# decoder.net
KiCad netlist of a schematic drawn in EAGLE
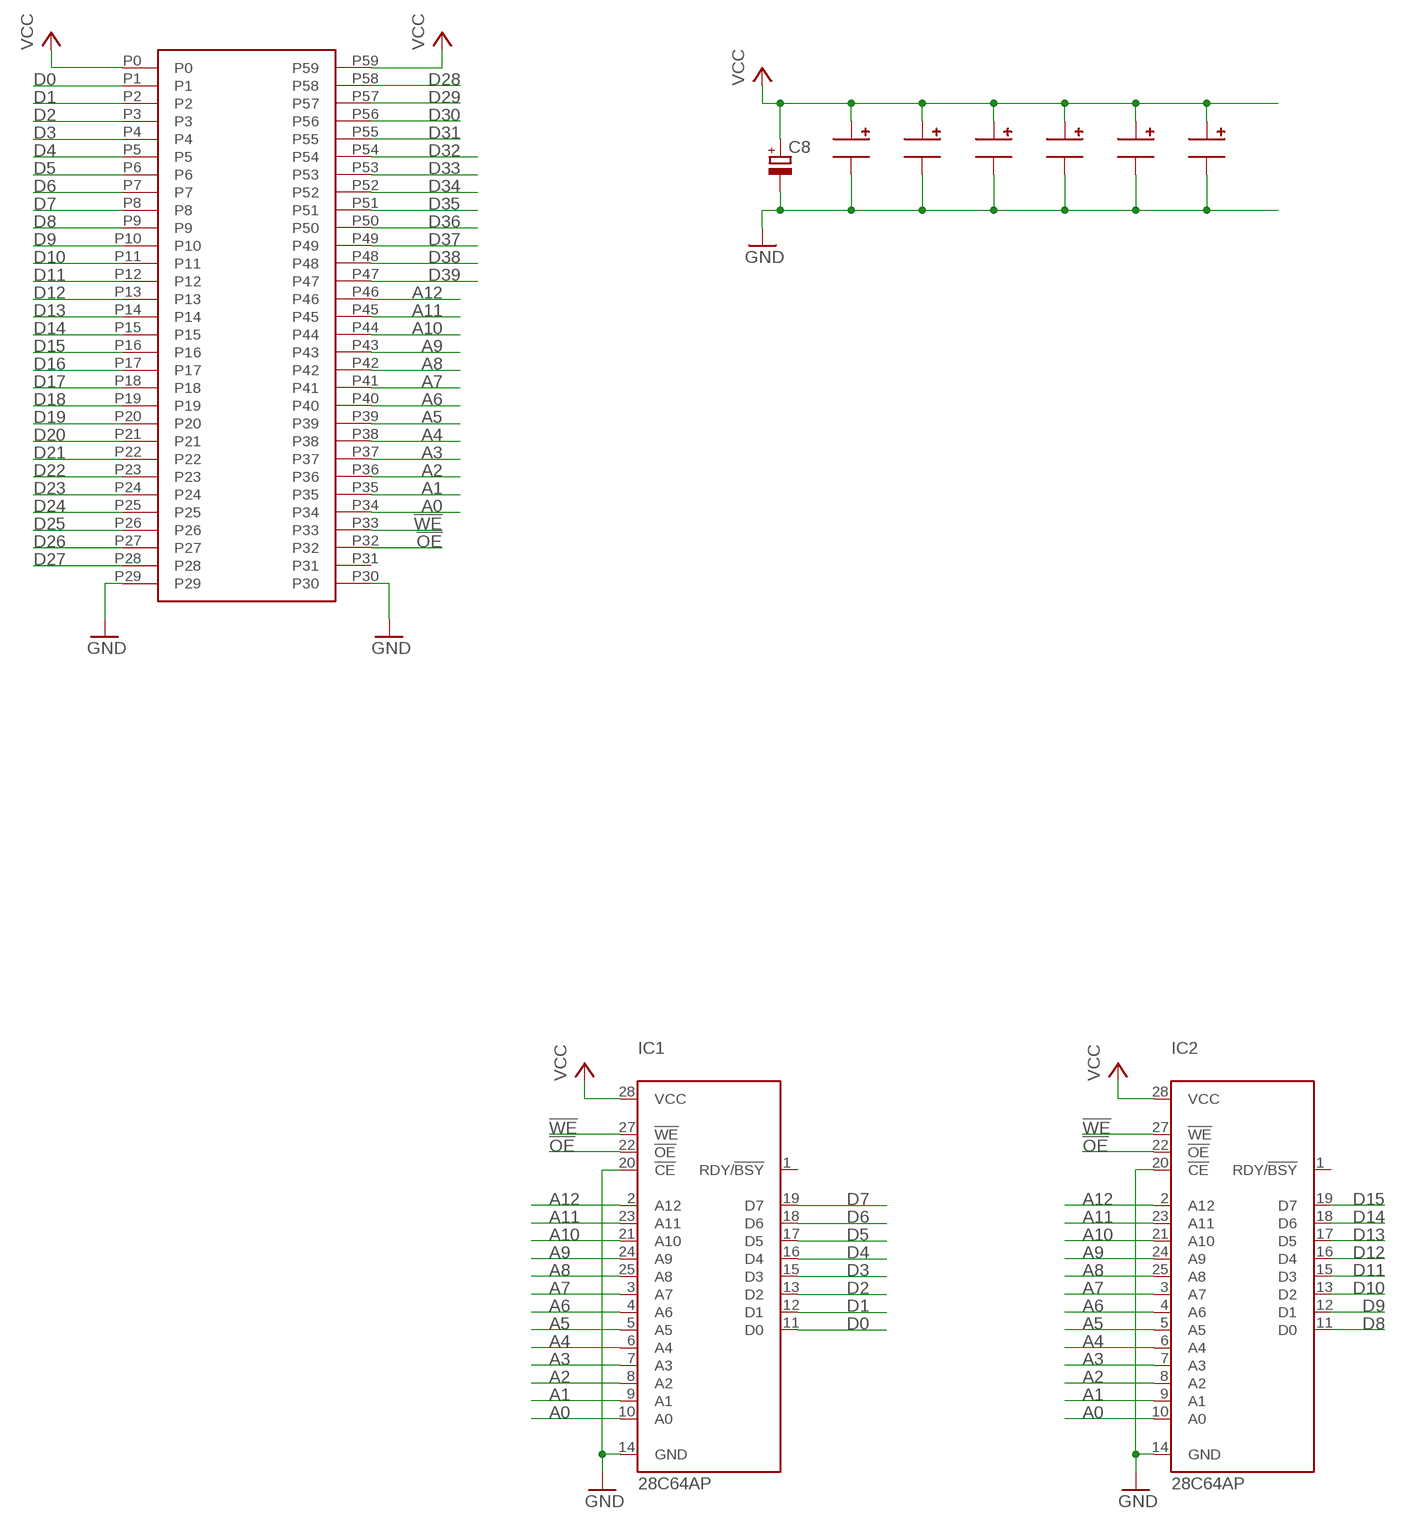
[diagram p0: schematic, sheet 1, part 1 of 2]
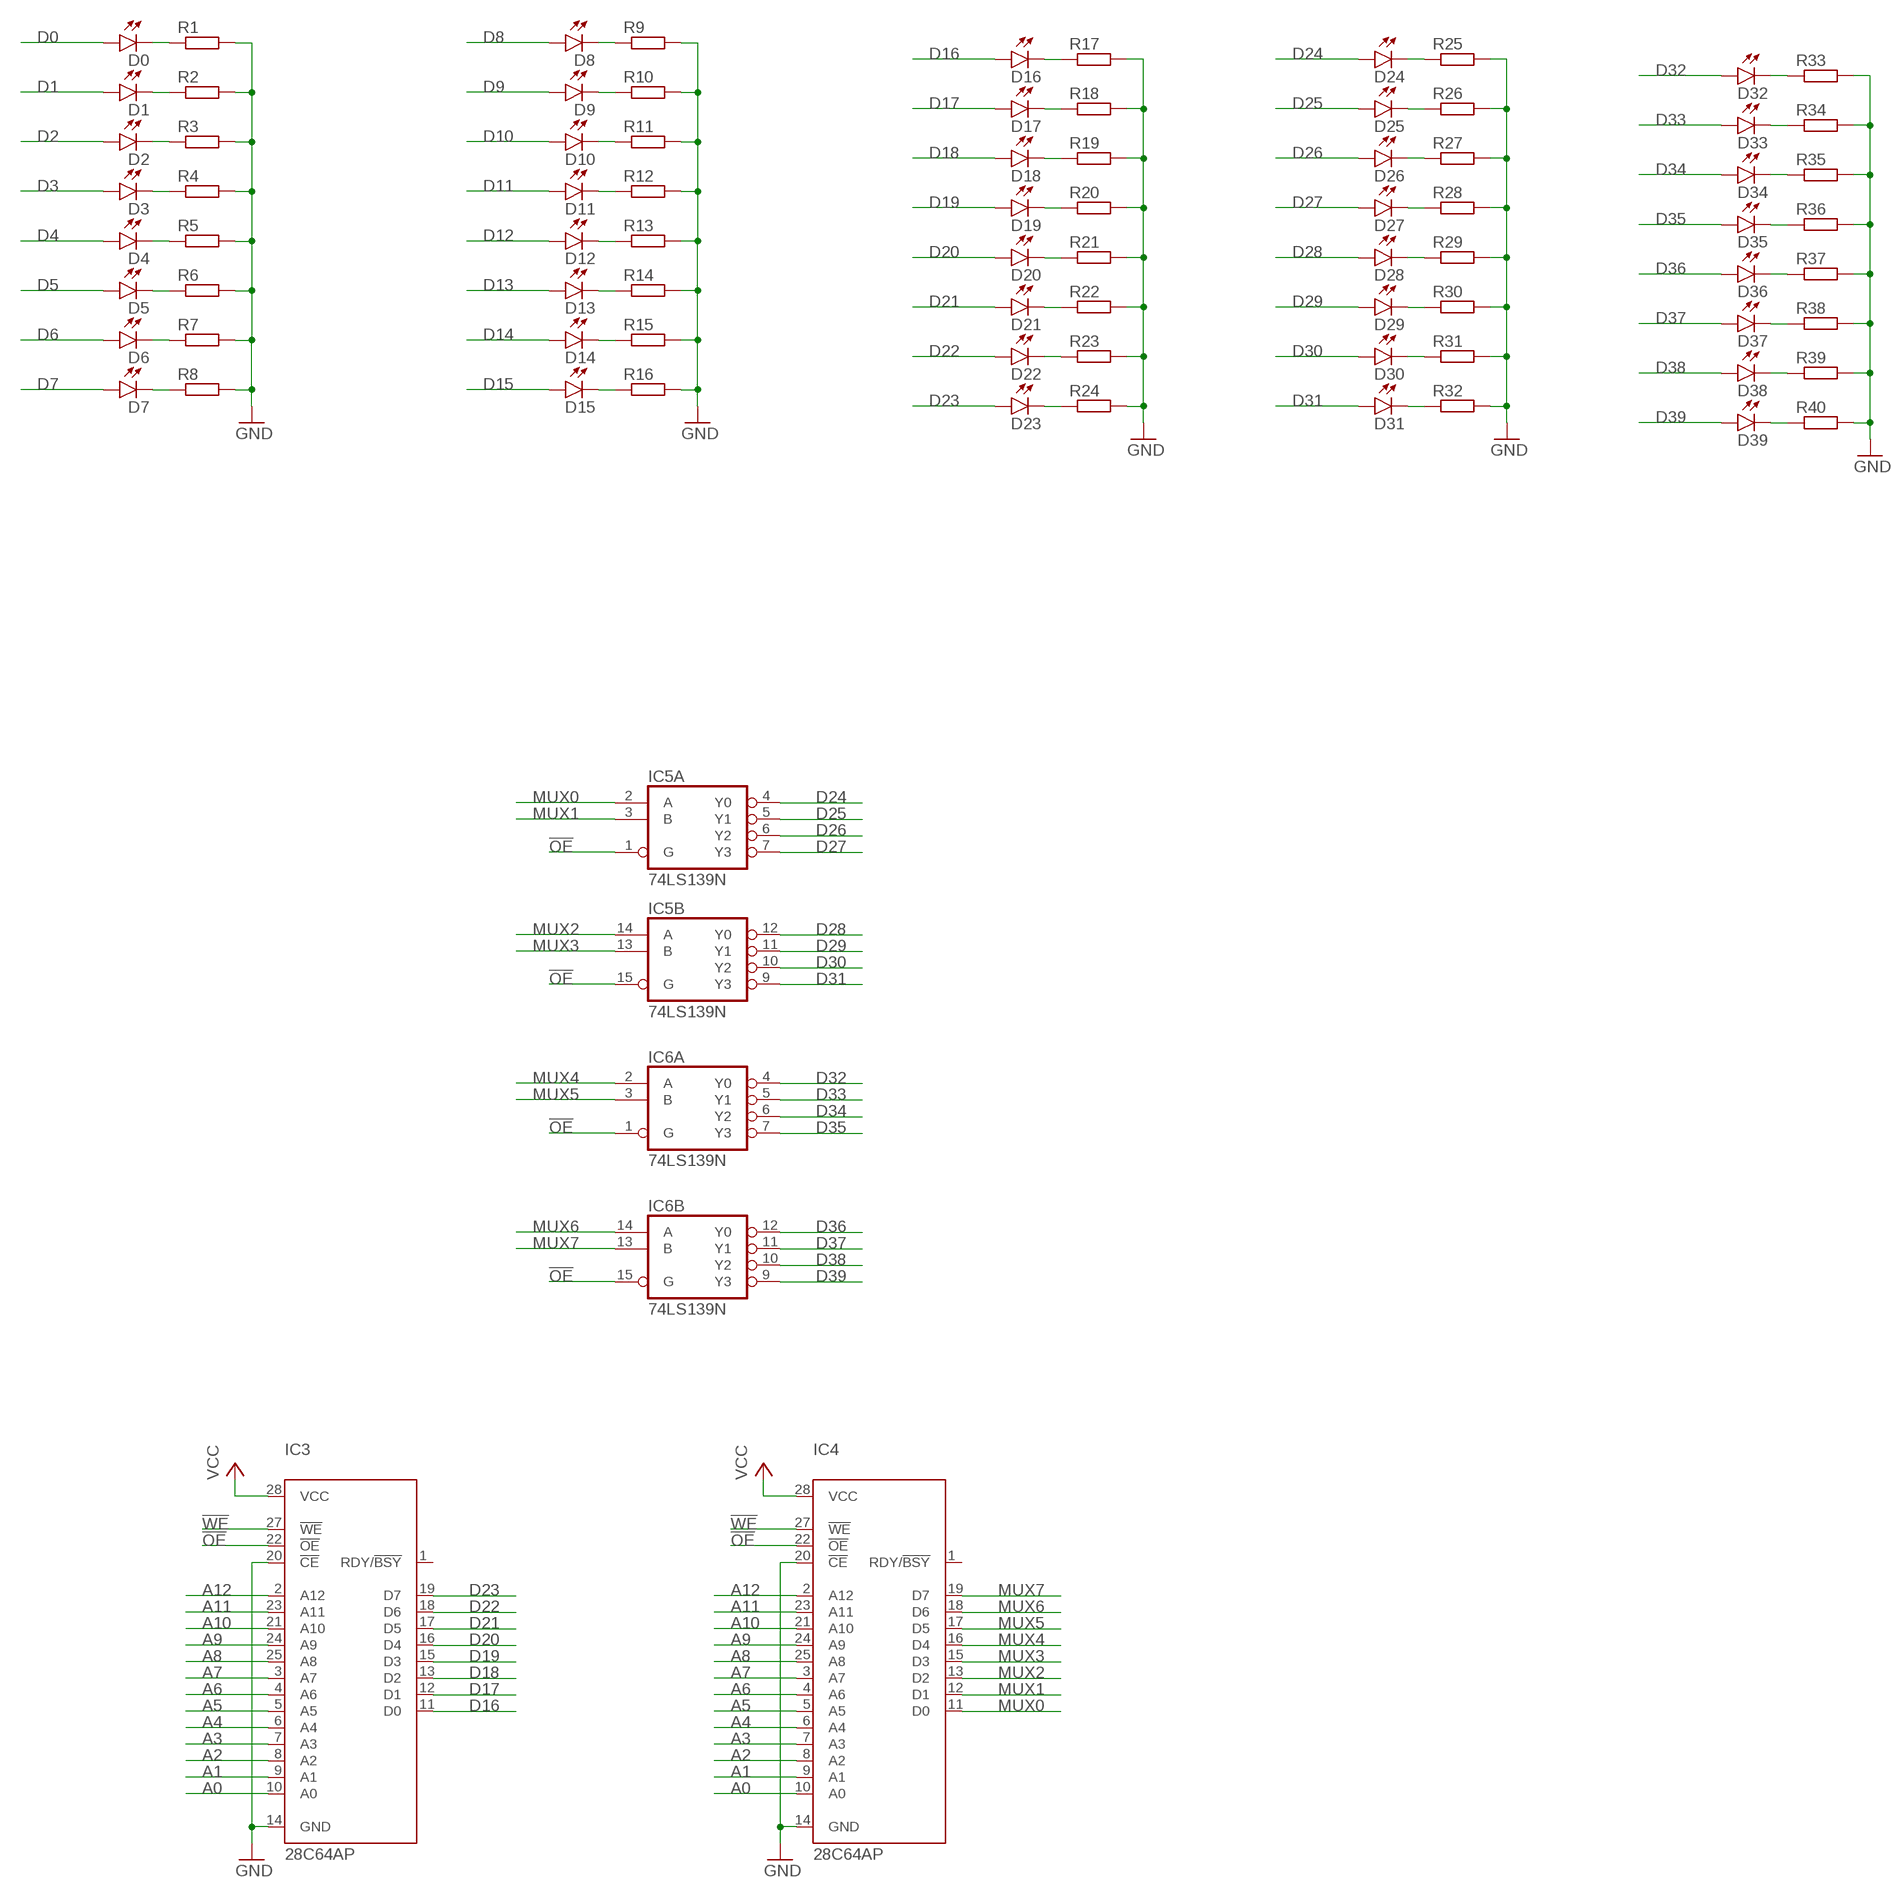
[diagram p1: schematic, sheet 1, part 2 of 2]

(export (version "E")
  (design (tool "Eeschema 10.0.6"))
  (components
    (comp (ref "C8")
      (value "CPOL-EUE2,5-6E")
      (footprint "eagle-import:E2,5-6E")
      (libsource (lib "eagle-import") (part "CPOL-EUE2,5-6E"))
    )
    (comp (ref "D0")
      (value "LEDSML1206")
      (footprint "eagle-import:SML1206")
      (libsource (lib "eagle-import") (part "LEDSML1206"))
    )
    (comp (ref "D1")
      (value "LEDSML1206")
      (footprint "eagle-import:SML1206")
      (libsource (lib "eagle-import") (part "LEDSML1206"))
    )
    (comp (ref "D2")
      (value "LEDSML1206")
      (footprint "eagle-import:SML1206")
      (libsource (lib "eagle-import") (part "LEDSML1206"))
    )
    (comp (ref "D3")
      (value "LEDSML1206")
      (footprint "eagle-import:SML1206")
      (libsource (lib "eagle-import") (part "LEDSML1206"))
    )
    (comp (ref "D4")
      (value "LEDSML1206")
      (footprint "eagle-import:SML1206")
      (libsource (lib "eagle-import") (part "LEDSML1206"))
    )
    (comp (ref "D5")
      (value "LEDSML1206")
      (footprint "eagle-import:SML1206")
      (libsource (lib "eagle-import") (part "LEDSML1206"))
    )
    (comp (ref "D6")
      (value "LEDSML1206")
      (footprint "eagle-import:SML1206")
      (libsource (lib "eagle-import") (part "LEDSML1206"))
    )
    (comp (ref "D7")
      (value "LEDSML1206")
      (footprint "eagle-import:SML1206")
      (libsource (lib "eagle-import") (part "LEDSML1206"))
    )
    (comp (ref "D8")
      (value "LEDSML1206")
      (footprint "eagle-import:SML1206")
      (libsource (lib "eagle-import") (part "LEDSML1206"))
    )
    (comp (ref "D9")
      (value "LEDSML1206")
      (footprint "eagle-import:SML1206")
      (libsource (lib "eagle-import") (part "LEDSML1206"))
    )
    (comp (ref "D10")
      (value "LEDSML1206")
      (footprint "eagle-import:SML1206")
      (libsource (lib "eagle-import") (part "LEDSML1206"))
    )
    (comp (ref "D11")
      (value "LEDSML1206")
      (footprint "eagle-import:SML1206")
      (libsource (lib "eagle-import") (part "LEDSML1206"))
    )
    (comp (ref "D12")
      (value "LEDSML1206")
      (footprint "eagle-import:SML1206")
      (libsource (lib "eagle-import") (part "LEDSML1206"))
    )
    (comp (ref "D13")
      (value "LEDSML1206")
      (footprint "eagle-import:SML1206")
      (libsource (lib "eagle-import") (part "LEDSML1206"))
    )
    (comp (ref "D14")
      (value "LEDSML1206")
      (footprint "eagle-import:SML1206")
      (libsource (lib "eagle-import") (part "LEDSML1206"))
    )
    (comp (ref "D15")
      (value "LEDSML1206")
      (footprint "eagle-import:SML1206")
      (libsource (lib "eagle-import") (part "LEDSML1206"))
    )
    (comp (ref "D16")
      (value "LEDSML1206")
      (footprint "eagle-import:SML1206")
      (libsource (lib "eagle-import") (part "LEDSML1206"))
    )
    (comp (ref "D17")
      (value "LEDSML1206")
      (footprint "eagle-import:SML1206")
      (libsource (lib "eagle-import") (part "LEDSML1206"))
    )
    (comp (ref "D18")
      (value "LEDSML1206")
      (footprint "eagle-import:SML1206")
      (libsource (lib "eagle-import") (part "LEDSML1206"))
    )
    (comp (ref "D19")
      (value "LEDSML1206")
      (footprint "eagle-import:SML1206")
      (libsource (lib "eagle-import") (part "LEDSML1206"))
    )
    (comp (ref "D20")
      (value "LEDSML1206")
      (footprint "eagle-import:SML1206")
      (libsource (lib "eagle-import") (part "LEDSML1206"))
    )
    (comp (ref "D21")
      (value "LEDSML1206")
      (footprint "eagle-import:SML1206")
      (libsource (lib "eagle-import") (part "LEDSML1206"))
    )
    (comp (ref "D22")
      (value "LEDSML1206")
      (footprint "eagle-import:SML1206")
      (libsource (lib "eagle-import") (part "LEDSML1206"))
    )
    (comp (ref "D23")
      (value "LEDSML1206")
      (footprint "eagle-import:SML1206")
      (libsource (lib "eagle-import") (part "LEDSML1206"))
    )
    (comp (ref "D24")
      (value "LEDSML1206")
      (footprint "eagle-import:SML1206")
      (libsource (lib "eagle-import") (part "LEDSML1206"))
    )
    (comp (ref "D25")
      (value "LEDSML1206")
      (footprint "eagle-import:SML1206")
      (libsource (lib "eagle-import") (part "LEDSML1206"))
    )
    (comp (ref "D26")
      (value "LEDSML1206")
      (footprint "eagle-import:SML1206")
      (libsource (lib "eagle-import") (part "LEDSML1206"))
    )
    (comp (ref "D27")
      (value "LEDSML1206")
      (footprint "eagle-import:SML1206")
      (libsource (lib "eagle-import") (part "LEDSML1206"))
    )
    (comp (ref "D28")
      (value "LEDSML1206")
      (footprint "eagle-import:SML1206")
      (libsource (lib "eagle-import") (part "LEDSML1206"))
    )
    (comp (ref "D29")
      (value "LEDSML1206")
      (footprint "eagle-import:SML1206")
      (libsource (lib "eagle-import") (part "LEDSML1206"))
    )
    (comp (ref "D30")
      (value "LEDSML1206")
      (footprint "eagle-import:SML1206")
      (libsource (lib "eagle-import") (part "LEDSML1206"))
    )
    (comp (ref "D31")
      (value "LEDSML1206")
      (footprint "eagle-import:SML1206")
      (libsource (lib "eagle-import") (part "LEDSML1206"))
    )
    (comp (ref "D32")
      (value "LEDSML1206")
      (footprint "eagle-import:SML1206")
      (libsource (lib "eagle-import") (part "LEDSML1206"))
    )
    (comp (ref "D33")
      (value "LEDSML1206")
      (footprint "eagle-import:SML1206")
      (libsource (lib "eagle-import") (part "LEDSML1206"))
    )
    (comp (ref "D34")
      (value "LEDSML1206")
      (footprint "eagle-import:SML1206")
      (libsource (lib "eagle-import") (part "LEDSML1206"))
    )
    (comp (ref "D35")
      (value "LEDSML1206")
      (footprint "eagle-import:SML1206")
      (libsource (lib "eagle-import") (part "LEDSML1206"))
    )
    (comp (ref "D36")
      (value "LEDSML1206")
      (footprint "eagle-import:SML1206")
      (libsource (lib "eagle-import") (part "LEDSML1206"))
    )
    (comp (ref "D37")
      (value "LEDSML1206")
      (footprint "eagle-import:SML1206")
      (libsource (lib "eagle-import") (part "LEDSML1206"))
    )
    (comp (ref "D38")
      (value "LEDSML1206")
      (footprint "eagle-import:SML1206")
      (libsource (lib "eagle-import") (part "LEDSML1206"))
    )
    (comp (ref "D39")
      (value "LEDSML1206")
      (footprint "eagle-import:SML1206")
      (libsource (lib "eagle-import") (part "LEDSML1206"))
    )
    (comp (ref "IC1")
      (value "28C64AP")
      (footprint "eagle-import:DIL28-6")
      (fields (field (name "MPN") "AT28C64B-15PU"))
      (libsource (lib "eagle-import") (part "2864APC"))
    )
    (comp (ref "IC2")
      (value "28C64AP")
      (footprint "eagle-import:DIL28-6")
      (fields (field (name "MPN") "AT28C64B-15PU"))
      (libsource (lib "eagle-import") (part "2864APC"))
    )
    (comp (ref "IC3")
      (value "28C64AP")
      (footprint "eagle-import:DIL28-6")
      (fields (field (name "MPN") "AT28C64B-15PU"))
      (libsource (lib "eagle-import") (part "2864APC"))
    )
    (comp (ref "IC4")
      (value "28C64AP")
      (footprint "eagle-import:DIL28-6")
      (fields (field (name "MPN") "AT28C64B-15PU"))
      (libsource (lib "eagle-import") (part "2864APC"))
    )
    (comp (ref "IC5")
      (value "74LS139N")
      (footprint "eagle-import:DIL16")
      (libsource (lib "eagle-import") (part "74139NLS"))
    )
    (comp (ref "IC6")
      (value "74LS139N")
      (footprint "eagle-import:DIL16")
      (libsource (lib "eagle-import") (part "74139NLS"))
    )
    (comp (ref "R1")
      (value "R-EU_R0805")
      (footprint "eagle-import:R0805")
      (libsource (lib "eagle-import") (part "R-EU_R0805"))
    )
    (comp (ref "R2")
      (value "R-EU_R0805")
      (footprint "eagle-import:R0805")
      (libsource (lib "eagle-import") (part "R-EU_R0805"))
    )
    (comp (ref "R3")
      (value "R-EU_R0805")
      (footprint "eagle-import:R0805")
      (libsource (lib "eagle-import") (part "R-EU_R0805"))
    )
    (comp (ref "R4")
      (value "R-EU_R0805")
      (footprint "eagle-import:R0805")
      (libsource (lib "eagle-import") (part "R-EU_R0805"))
    )
    (comp (ref "R5")
      (value "R-EU_R0805")
      (footprint "eagle-import:R0805")
      (libsource (lib "eagle-import") (part "R-EU_R0805"))
    )
    (comp (ref "R6")
      (value "R-EU_R0805")
      (footprint "eagle-import:R0805")
      (libsource (lib "eagle-import") (part "R-EU_R0805"))
    )
    (comp (ref "R7")
      (value "R-EU_R0805")
      (footprint "eagle-import:R0805")
      (libsource (lib "eagle-import") (part "R-EU_R0805"))
    )
    (comp (ref "R8")
      (value "R-EU_R0805")
      (footprint "eagle-import:R0805")
      (libsource (lib "eagle-import") (part "R-EU_R0805"))
    )
    (comp (ref "R9")
      (value "R-EU_R0805")
      (footprint "eagle-import:R0805")
      (libsource (lib "eagle-import") (part "R-EU_R0805"))
    )
    (comp (ref "R10")
      (value "R-EU_R0805")
      (footprint "eagle-import:R0805")
      (libsource (lib "eagle-import") (part "R-EU_R0805"))
    )
    (comp (ref "R11")
      (value "R-EU_R0805")
      (footprint "eagle-import:R0805")
      (libsource (lib "eagle-import") (part "R-EU_R0805"))
    )
    (comp (ref "R12")
      (value "R-EU_R0805")
      (footprint "eagle-import:R0805")
      (libsource (lib "eagle-import") (part "R-EU_R0805"))
    )
    (comp (ref "R13")
      (value "R-EU_R0805")
      (footprint "eagle-import:R0805")
      (libsource (lib "eagle-import") (part "R-EU_R0805"))
    )
    (comp (ref "R14")
      (value "R-EU_R0805")
      (footprint "eagle-import:R0805")
      (libsource (lib "eagle-import") (part "R-EU_R0805"))
    )
    (comp (ref "R15")
      (value "R-EU_R0805")
      (footprint "eagle-import:R0805")
      (libsource (lib "eagle-import") (part "R-EU_R0805"))
    )
    (comp (ref "R16")
      (value "R-EU_R0805")
      (footprint "eagle-import:R0805")
      (libsource (lib "eagle-import") (part "R-EU_R0805"))
    )
    (comp (ref "R17")
      (value "R-EU_R0805")
      (footprint "eagle-import:R0805")
      (libsource (lib "eagle-import") (part "R-EU_R0805"))
    )
    (comp (ref "R18")
      (value "R-EU_R0805")
      (footprint "eagle-import:R0805")
      (libsource (lib "eagle-import") (part "R-EU_R0805"))
    )
    (comp (ref "R19")
      (value "R-EU_R0805")
      (footprint "eagle-import:R0805")
      (libsource (lib "eagle-import") (part "R-EU_R0805"))
    )
    (comp (ref "R20")
      (value "R-EU_R0805")
      (footprint "eagle-import:R0805")
      (libsource (lib "eagle-import") (part "R-EU_R0805"))
    )
    (comp (ref "R21")
      (value "R-EU_R0805")
      (footprint "eagle-import:R0805")
      (libsource (lib "eagle-import") (part "R-EU_R0805"))
    )
    (comp (ref "R22")
      (value "R-EU_R0805")
      (footprint "eagle-import:R0805")
      (libsource (lib "eagle-import") (part "R-EU_R0805"))
    )
    (comp (ref "R23")
      (value "R-EU_R0805")
      (footprint "eagle-import:R0805")
      (libsource (lib "eagle-import") (part "R-EU_R0805"))
    )
    (comp (ref "R24")
      (value "R-EU_R0805")
      (footprint "eagle-import:R0805")
      (libsource (lib "eagle-import") (part "R-EU_R0805"))
    )
    (comp (ref "R25")
      (value "R-EU_R0805")
      (footprint "eagle-import:R0805")
      (libsource (lib "eagle-import") (part "R-EU_R0805"))
    )
    (comp (ref "R26")
      (value "R-EU_R0805")
      (footprint "eagle-import:R0805")
      (libsource (lib "eagle-import") (part "R-EU_R0805"))
    )
    (comp (ref "R27")
      (value "R-EU_R0805")
      (footprint "eagle-import:R0805")
      (libsource (lib "eagle-import") (part "R-EU_R0805"))
    )
    (comp (ref "R28")
      (value "R-EU_R0805")
      (footprint "eagle-import:R0805")
      (libsource (lib "eagle-import") (part "R-EU_R0805"))
    )
    (comp (ref "R29")
      (value "R-EU_R0805")
      (footprint "eagle-import:R0805")
      (libsource (lib "eagle-import") (part "R-EU_R0805"))
    )
    (comp (ref "R30")
      (value "R-EU_R0805")
      (footprint "eagle-import:R0805")
      (libsource (lib "eagle-import") (part "R-EU_R0805"))
    )
    (comp (ref "R31")
      (value "R-EU_R0805")
      (footprint "eagle-import:R0805")
      (libsource (lib "eagle-import") (part "R-EU_R0805"))
    )
    (comp (ref "R32")
      (value "R-EU_R0805")
      (footprint "eagle-import:R0805")
      (libsource (lib "eagle-import") (part "R-EU_R0805"))
    )
    (comp (ref "R33")
      (value "R-EU_R0805")
      (footprint "eagle-import:R0805")
      (libsource (lib "eagle-import") (part "R-EU_R0805"))
    )
    (comp (ref "R34")
      (value "R-EU_R0805")
      (footprint "eagle-import:R0805")
      (libsource (lib "eagle-import") (part "R-EU_R0805"))
    )
    (comp (ref "R35")
      (value "R-EU_R0805")
      (footprint "eagle-import:R0805")
      (libsource (lib "eagle-import") (part "R-EU_R0805"))
    )
    (comp (ref "R36")
      (value "R-EU_R0805")
      (footprint "eagle-import:R0805")
      (libsource (lib "eagle-import") (part "R-EU_R0805"))
    )
    (comp (ref "R37")
      (value "R-EU_R0805")
      (footprint "eagle-import:R0805")
      (libsource (lib "eagle-import") (part "R-EU_R0805"))
    )
    (comp (ref "R38")
      (value "R-EU_R0805")
      (footprint "eagle-import:R0805")
      (libsource (lib "eagle-import") (part "R-EU_R0805"))
    )
    (comp (ref "R39")
      (value "R-EU_R0805")
      (footprint "eagle-import:R0805")
      (libsource (lib "eagle-import") (part "R-EU_R0805"))
    )
    (comp (ref "R40")
      (value "R-EU_R0805")
      (footprint "eagle-import:R0805")
      (libsource (lib "eagle-import") (part "R-EU_R0805"))
    )
    (comp (ref "U$1")
      (value "2X60")
      (footprint "eagle-import:2X60")
      (libsource (lib "eagle-import") (part "2X60"))
    )
    (comp (ref "U$2")
      (value "CAP")
      (footprint "eagle-import:CAP")
      (libsource (lib "eagle-import") (part "CAP"))
    )
    (comp (ref "U$3")
      (value "CAP")
      (footprint "eagle-import:CAP")
      (libsource (lib "eagle-import") (part "CAP"))
    )
    (comp (ref "U$4")
      (value "CAP")
      (footprint "eagle-import:CAP")
      (libsource (lib "eagle-import") (part "CAP"))
    )
    (comp (ref "U$5")
      (value "CAP")
      (footprint "eagle-import:CAP")
      (libsource (lib "eagle-import") (part "CAP"))
    )
    (comp (ref "U$6")
      (value "CAP")
      (footprint "eagle-import:CAP")
      (libsource (lib "eagle-import") (part "CAP"))
    )
    (comp (ref "U$7")
      (value "CAP")
      (footprint "eagle-import:CAP")
      (libsource (lib "eagle-import") (part "CAP"))
    )
  )
  (nets
    (net (code "1") (name "/A0") (class "Default")
      (node (ref "IC1") (pin "10") (pinfunction "A0_10") (pintype "input"))
      (node (ref "IC2") (pin "10") (pinfunction "A0_10") (pintype "input"))
      (node (ref "IC3") (pin "10") (pinfunction "A0_10") (pintype "input"))
      (node (ref "IC4") (pin "10") (pinfunction "A0_10") (pintype "input"))
      (node (ref "U$1") (pin "P34") (pinfunction "P34_P34") (pintype "bidirectional"))
    )
    (net (code "2") (name "/A1") (class "Default")
      (node (ref "IC1") (pin "9") (pinfunction "A1_9") (pintype "input"))
      (node (ref "IC2") (pin "9") (pinfunction "A1_9") (pintype "input"))
      (node (ref "IC3") (pin "9") (pinfunction "A1_9") (pintype "input"))
      (node (ref "IC4") (pin "9") (pinfunction "A1_9") (pintype "input"))
      (node (ref "U$1") (pin "P35") (pinfunction "P35_P35") (pintype "bidirectional"))
    )
    (net (code "3") (name "/A2") (class "Default")
      (node (ref "IC1") (pin "8") (pinfunction "A2_8") (pintype "input"))
      (node (ref "IC2") (pin "8") (pinfunction "A2_8") (pintype "input"))
      (node (ref "IC3") (pin "8") (pinfunction "A2_8") (pintype "input"))
      (node (ref "IC4") (pin "8") (pinfunction "A2_8") (pintype "input"))
      (node (ref "U$1") (pin "P36") (pinfunction "P36_P36") (pintype "bidirectional"))
    )
    (net (code "4") (name "/A3") (class "Default")
      (node (ref "IC1") (pin "7") (pinfunction "A3_7") (pintype "input"))
      (node (ref "IC2") (pin "7") (pinfunction "A3_7") (pintype "input"))
      (node (ref "IC3") (pin "7") (pinfunction "A3_7") (pintype "input"))
      (node (ref "IC4") (pin "7") (pinfunction "A3_7") (pintype "input"))
      (node (ref "U$1") (pin "P37") (pinfunction "P37_P37") (pintype "bidirectional"))
    )
    (net (code "5") (name "/A4") (class "Default")
      (node (ref "IC1") (pin "6") (pinfunction "A4_6") (pintype "input"))
      (node (ref "IC2") (pin "6") (pinfunction "A4_6") (pintype "input"))
      (node (ref "IC3") (pin "6") (pinfunction "A4_6") (pintype "input"))
      (node (ref "IC4") (pin "6") (pinfunction "A4_6") (pintype "input"))
      (node (ref "U$1") (pin "P38") (pinfunction "P38_P38") (pintype "bidirectional"))
    )
    (net (code "6") (name "/A5") (class "Default")
      (node (ref "IC1") (pin "5") (pinfunction "A5_5") (pintype "input"))
      (node (ref "IC2") (pin "5") (pinfunction "A5_5") (pintype "input"))
      (node (ref "IC3") (pin "5") (pinfunction "A5_5") (pintype "input"))
      (node (ref "IC4") (pin "5") (pinfunction "A5_5") (pintype "input"))
      (node (ref "U$1") (pin "P39") (pinfunction "P39_P39") (pintype "bidirectional"))
    )
    (net (code "7") (name "/A6") (class "Default")
      (node (ref "IC1") (pin "4") (pinfunction "A6_4") (pintype "input"))
      (node (ref "IC2") (pin "4") (pinfunction "A6_4") (pintype "input"))
      (node (ref "IC3") (pin "4") (pinfunction "A6_4") (pintype "input"))
      (node (ref "IC4") (pin "4") (pinfunction "A6_4") (pintype "input"))
      (node (ref "U$1") (pin "P40") (pinfunction "P40_P40") (pintype "bidirectional"))
    )
    (net (code "8") (name "/A7") (class "Default")
      (node (ref "IC1") (pin "3") (pinfunction "A7_3") (pintype "input"))
      (node (ref "IC2") (pin "3") (pinfunction "A7_3") (pintype "input"))
      (node (ref "IC3") (pin "3") (pinfunction "A7_3") (pintype "input"))
      (node (ref "IC4") (pin "3") (pinfunction "A7_3") (pintype "input"))
      (node (ref "U$1") (pin "P41") (pinfunction "P41_P41") (pintype "bidirectional"))
    )
    (net (code "9") (name "/A8") (class "Default")
      (node (ref "IC1") (pin "25") (pinfunction "A8_25") (pintype "input"))
      (node (ref "IC2") (pin "25") (pinfunction "A8_25") (pintype "input"))
      (node (ref "IC3") (pin "25") (pinfunction "A8_25") (pintype "input"))
      (node (ref "IC4") (pin "25") (pinfunction "A8_25") (pintype "input"))
      (node (ref "U$1") (pin "P42") (pinfunction "P42_P42") (pintype "bidirectional"))
    )
    (net (code "10") (name "/A9") (class "Default")
      (node (ref "IC1") (pin "24") (pinfunction "A9_24") (pintype "input"))
      (node (ref "IC2") (pin "24") (pinfunction "A9_24") (pintype "input"))
      (node (ref "IC3") (pin "24") (pinfunction "A9_24") (pintype "input"))
      (node (ref "IC4") (pin "24") (pinfunction "A9_24") (pintype "input"))
      (node (ref "U$1") (pin "P43") (pinfunction "P43_P43") (pintype "bidirectional"))
    )
    (net (code "11") (name "/A10") (class "Default")
      (node (ref "IC1") (pin "21") (pinfunction "A10_21") (pintype "input"))
      (node (ref "IC2") (pin "21") (pinfunction "A10_21") (pintype "input"))
      (node (ref "IC3") (pin "21") (pinfunction "A10_21") (pintype "input"))
      (node (ref "IC4") (pin "21") (pinfunction "A10_21") (pintype "input"))
      (node (ref "U$1") (pin "P44") (pinfunction "P44_P44") (pintype "bidirectional"))
    )
    (net (code "12") (name "/A11") (class "Default")
      (node (ref "IC1") (pin "23") (pinfunction "A11_23") (pintype "input"))
      (node (ref "IC2") (pin "23") (pinfunction "A11_23") (pintype "input"))
      (node (ref "IC3") (pin "23") (pinfunction "A11_23") (pintype "input"))
      (node (ref "IC4") (pin "23") (pinfunction "A11_23") (pintype "input"))
      (node (ref "U$1") (pin "P45") (pinfunction "P45_P45") (pintype "bidirectional"))
    )
    (net (code "13") (name "/A12") (class "Default")
      (node (ref "IC1") (pin "2") (pinfunction "A12_2") (pintype "input"))
      (node (ref "IC2") (pin "2") (pinfunction "A12_2") (pintype "input"))
      (node (ref "IC3") (pin "2") (pinfunction "A12_2") (pintype "input"))
      (node (ref "IC4") (pin "2") (pinfunction "A12_2") (pintype "input"))
      (node (ref "U$1") (pin "P46") (pinfunction "P46_P46") (pintype "bidirectional"))
    )
    (net (code "14") (name "/D0") (class "Default")
      (node (ref "D0") (pin "A") (pinfunction "A_A") (pintype "passive"))
      (node (ref "IC1") (pin "11") (pinfunction "D0_11") (pintype "tri_state"))
      (node (ref "U$1") (pin "P1") (pinfunction "P1_P1") (pintype "bidirectional"))
    )
    (net (code "15") (name "/D1") (class "Default")
      (node (ref "D1") (pin "A") (pinfunction "A_A") (pintype "passive"))
      (node (ref "IC1") (pin "12") (pinfunction "D1_12") (pintype "tri_state"))
      (node (ref "U$1") (pin "P2") (pinfunction "P2_P2") (pintype "bidirectional"))
    )
    (net (code "16") (name "/D2") (class "Default")
      (node (ref "D2") (pin "A") (pinfunction "A_A") (pintype "passive"))
      (node (ref "IC1") (pin "13") (pinfunction "D2_13") (pintype "tri_state"))
      (node (ref "U$1") (pin "P3") (pinfunction "P3_P3") (pintype "bidirectional"))
    )
    (net (code "17") (name "/D3") (class "Default")
      (node (ref "D3") (pin "A") (pinfunction "A_A") (pintype "passive"))
      (node (ref "IC1") (pin "15") (pinfunction "D3_15") (pintype "tri_state"))
      (node (ref "U$1") (pin "P4") (pinfunction "P4_P4") (pintype "bidirectional"))
    )
    (net (code "18") (name "/D4") (class "Default")
      (node (ref "D4") (pin "A") (pinfunction "A_A") (pintype "passive"))
      (node (ref "IC1") (pin "16") (pinfunction "D4_16") (pintype "tri_state"))
      (node (ref "U$1") (pin "P5") (pinfunction "P5_P5") (pintype "bidirectional"))
    )
    (net (code "19") (name "/D5") (class "Default")
      (node (ref "D5") (pin "A") (pinfunction "A_A") (pintype "passive"))
      (node (ref "IC1") (pin "17") (pinfunction "D5_17") (pintype "tri_state"))
      (node (ref "U$1") (pin "P6") (pinfunction "P6_P6") (pintype "bidirectional"))
    )
    (net (code "20") (name "/D6") (class "Default")
      (node (ref "D6") (pin "A") (pinfunction "A_A") (pintype "passive"))
      (node (ref "IC1") (pin "18") (pinfunction "D6_18") (pintype "tri_state"))
      (node (ref "U$1") (pin "P7") (pinfunction "P7_P7") (pintype "bidirectional"))
    )
    (net (code "21") (name "/D7") (class "Default")
      (node (ref "D7") (pin "A") (pinfunction "A_A") (pintype "passive"))
      (node (ref "IC1") (pin "19") (pinfunction "D7_19") (pintype "tri_state"))
      (node (ref "U$1") (pin "P8") (pinfunction "P8_P8") (pintype "bidirectional"))
    )
    (net (code "22") (name "/D8") (class "Default")
      (node (ref "D8") (pin "A") (pinfunction "A_A") (pintype "passive"))
      (node (ref "IC2") (pin "11") (pinfunction "D0_11") (pintype "tri_state"))
      (node (ref "U$1") (pin "P9") (pinfunction "P9_P9") (pintype "bidirectional"))
    )
    (net (code "23") (name "/D9") (class "Default")
      (node (ref "D9") (pin "A") (pinfunction "A_A") (pintype "passive"))
      (node (ref "IC2") (pin "12") (pinfunction "D1_12") (pintype "tri_state"))
      (node (ref "U$1") (pin "P10") (pinfunction "P10_P10") (pintype "bidirectional"))
    )
    (net (code "24") (name "/D10") (class "Default")
      (node (ref "D10") (pin "A") (pinfunction "A_A") (pintype "passive"))
      (node (ref "IC2") (pin "13") (pinfunction "D2_13") (pintype "tri_state"))
      (node (ref "U$1") (pin "P11") (pinfunction "P11_P11") (pintype "bidirectional"))
    )
    (net (code "25") (name "/D11") (class "Default")
      (node (ref "D11") (pin "A") (pinfunction "A_A") (pintype "passive"))
      (node (ref "IC2") (pin "15") (pinfunction "D3_15") (pintype "tri_state"))
      (node (ref "U$1") (pin "P12") (pinfunction "P12_P12") (pintype "bidirectional"))
    )
    (net (code "26") (name "/D12") (class "Default")
      (node (ref "D12") (pin "A") (pinfunction "A_A") (pintype "passive"))
      (node (ref "IC2") (pin "16") (pinfunction "D4_16") (pintype "tri_state"))
      (node (ref "U$1") (pin "P13") (pinfunction "P13_P13") (pintype "bidirectional"))
    )
    (net (code "27") (name "/D13") (class "Default")
      (node (ref "D13") (pin "A") (pinfunction "A_A") (pintype "passive"))
      (node (ref "IC2") (pin "17") (pinfunction "D5_17") (pintype "tri_state"))
      (node (ref "U$1") (pin "P14") (pinfunction "P14_P14") (pintype "bidirectional"))
    )
    (net (code "28") (name "/D14") (class "Default")
      (node (ref "D14") (pin "A") (pinfunction "A_A") (pintype "passive"))
      (node (ref "IC2") (pin "18") (pinfunction "D6_18") (pintype "tri_state"))
      (node (ref "U$1") (pin "P15") (pinfunction "P15_P15") (pintype "bidirectional"))
    )
    (net (code "29") (name "/D15") (class "Default")
      (node (ref "D15") (pin "A") (pinfunction "A_A") (pintype "passive"))
      (node (ref "IC2") (pin "19") (pinfunction "D7_19") (pintype "tri_state"))
      (node (ref "U$1") (pin "P16") (pinfunction "P16_P16") (pintype "bidirectional"))
    )
    (net (code "30") (name "/D16") (class "Default")
      (node (ref "D16") (pin "A") (pinfunction "A_A") (pintype "passive"))
      (node (ref "IC3") (pin "11") (pinfunction "D0_11") (pintype "tri_state"))
      (node (ref "U$1") (pin "P17") (pinfunction "P17_P17") (pintype "bidirectional"))
    )
    (net (code "31") (name "/D17") (class "Default")
      (node (ref "D17") (pin "A") (pinfunction "A_A") (pintype "passive"))
      (node (ref "IC3") (pin "12") (pinfunction "D1_12") (pintype "tri_state"))
      (node (ref "U$1") (pin "P18") (pinfunction "P18_P18") (pintype "bidirectional"))
    )
    (net (code "32") (name "/D18") (class "Default")
      (node (ref "D18") (pin "A") (pinfunction "A_A") (pintype "passive"))
      (node (ref "IC3") (pin "13") (pinfunction "D2_13") (pintype "tri_state"))
      (node (ref "U$1") (pin "P19") (pinfunction "P19_P19") (pintype "bidirectional"))
    )
    (net (code "33") (name "/D19") (class "Default")
      (node (ref "D19") (pin "A") (pinfunction "A_A") (pintype "passive"))
      (node (ref "IC3") (pin "15") (pinfunction "D3_15") (pintype "tri_state"))
      (node (ref "U$1") (pin "P20") (pinfunction "P20_P20") (pintype "bidirectional"))
    )
    (net (code "34") (name "/D20") (class "Default")
      (node (ref "D20") (pin "A") (pinfunction "A_A") (pintype "passive"))
      (node (ref "IC3") (pin "16") (pinfunction "D4_16") (pintype "tri_state"))
      (node (ref "U$1") (pin "P21") (pinfunction "P21_P21") (pintype "bidirectional"))
    )
    (net (code "35") (name "/D21") (class "Default")
      (node (ref "D21") (pin "A") (pinfunction "A_A") (pintype "passive"))
      (node (ref "IC3") (pin "17") (pinfunction "D5_17") (pintype "tri_state"))
      (node (ref "U$1") (pin "P22") (pinfunction "P22_P22") (pintype "bidirectional"))
    )
    (net (code "36") (name "/D22") (class "Default")
      (node (ref "D22") (pin "A") (pinfunction "A_A") (pintype "passive"))
      (node (ref "IC3") (pin "18") (pinfunction "D6_18") (pintype "tri_state"))
      (node (ref "U$1") (pin "P23") (pinfunction "P23_P23") (pintype "bidirectional"))
    )
    (net (code "37") (name "/D23") (class "Default")
      (node (ref "D23") (pin "A") (pinfunction "A_A") (pintype "passive"))
      (node (ref "IC3") (pin "19") (pinfunction "D7_19") (pintype "tri_state"))
      (node (ref "U$1") (pin "P24") (pinfunction "P24_P24") (pintype "bidirectional"))
    )
    (net (code "38") (name "/D24") (class "Default")
      (node (ref "D24") (pin "A") (pinfunction "A_A") (pintype "passive"))
      (node (ref "IC5") (pin "4") (pinfunction "Y0_4") (pintype "output"))
      (node (ref "U$1") (pin "P25") (pinfunction "P25_P25") (pintype "bidirectional"))
    )
    (net (code "39") (name "/D25") (class "Default")
      (node (ref "D25") (pin "A") (pinfunction "A_A") (pintype "passive"))
      (node (ref "IC5") (pin "5") (pinfunction "Y1_5") (pintype "output"))
      (node (ref "U$1") (pin "P26") (pinfunction "P26_P26") (pintype "bidirectional"))
    )
    (net (code "40") (name "/D26") (class "Default")
      (node (ref "D26") (pin "A") (pinfunction "A_A") (pintype "passive"))
      (node (ref "IC5") (pin "6") (pinfunction "Y2_6") (pintype "output"))
      (node (ref "U$1") (pin "P27") (pinfunction "P27_P27") (pintype "bidirectional"))
    )
    (net (code "41") (name "/D27") (class "Default")
      (node (ref "D27") (pin "A") (pinfunction "A_A") (pintype "passive"))
      (node (ref "IC5") (pin "7") (pinfunction "Y3_7") (pintype "output"))
      (node (ref "U$1") (pin "P28") (pinfunction "P28_P28") (pintype "bidirectional"))
    )
    (net (code "42") (name "/D28") (class "Default")
      (node (ref "D28") (pin "A") (pinfunction "A_A") (pintype "passive"))
      (node (ref "IC5") (pin "12") (pinfunction "Y0_12") (pintype "output"))
      (node (ref "U$1") (pin "P58") (pinfunction "P58_P58") (pintype "bidirectional"))
    )
    (net (code "43") (name "/D29") (class "Default")
      (node (ref "D29") (pin "A") (pinfunction "A_A") (pintype "passive"))
      (node (ref "IC5") (pin "11") (pinfunction "Y1_11") (pintype "output"))
      (node (ref "U$1") (pin "P57") (pinfunction "P57_P57") (pintype "bidirectional"))
    )
    (net (code "44") (name "/D30") (class "Default")
      (node (ref "D30") (pin "A") (pinfunction "A_A") (pintype "passive"))
      (node (ref "IC5") (pin "10") (pinfunction "Y2_10") (pintype "output"))
      (node (ref "U$1") (pin "P56") (pinfunction "P56_P56") (pintype "bidirectional"))
    )
    (net (code "45") (name "/D31") (class "Default")
      (node (ref "D31") (pin "A") (pinfunction "A_A") (pintype "passive"))
      (node (ref "IC5") (pin "9") (pinfunction "Y3_9") (pintype "output"))
      (node (ref "U$1") (pin "P55") (pinfunction "P55_P55") (pintype "bidirectional"))
    )
    (net (code "46") (name "/D32") (class "Default")
      (node (ref "D32") (pin "A") (pinfunction "A_A") (pintype "passive"))
      (node (ref "IC6") (pin "4") (pinfunction "Y0_4") (pintype "output"))
      (node (ref "U$1") (pin "P54") (pinfunction "P54_P54") (pintype "bidirectional"))
    )
    (net (code "47") (name "/D33") (class "Default")
      (node (ref "D33") (pin "A") (pinfunction "A_A") (pintype "passive"))
      (node (ref "IC6") (pin "5") (pinfunction "Y1_5") (pintype "output"))
      (node (ref "U$1") (pin "P53") (pinfunction "P53_P53") (pintype "bidirectional"))
    )
    (net (code "48") (name "/D34") (class "Default")
      (node (ref "D34") (pin "A") (pinfunction "A_A") (pintype "passive"))
      (node (ref "IC6") (pin "6") (pinfunction "Y2_6") (pintype "output"))
      (node (ref "U$1") (pin "P52") (pinfunction "P52_P52") (pintype "bidirectional"))
    )
    (net (code "49") (name "/D35") (class "Default")
      (node (ref "D35") (pin "A") (pinfunction "A_A") (pintype "passive"))
      (node (ref "IC6") (pin "7") (pinfunction "Y3_7") (pintype "output"))
      (node (ref "U$1") (pin "P51") (pinfunction "P51_P51") (pintype "bidirectional"))
    )
    (net (code "50") (name "/D36") (class "Default")
      (node (ref "D36") (pin "A") (pinfunction "A_A") (pintype "passive"))
      (node (ref "IC6") (pin "12") (pinfunction "Y0_12") (pintype "output"))
      (node (ref "U$1") (pin "P50") (pinfunction "P50_P50") (pintype "bidirectional"))
    )
    (net (code "51") (name "/D37") (class "Default")
      (node (ref "D37") (pin "A") (pinfunction "A_A") (pintype "passive"))
      (node (ref "IC6") (pin "11") (pinfunction "Y1_11") (pintype "output"))
      (node (ref "U$1") (pin "P49") (pinfunction "P49_P49") (pintype "bidirectional"))
    )
    (net (code "52") (name "/D38") (class "Default")
      (node (ref "D38") (pin "A") (pinfunction "A_A") (pintype "passive"))
      (node (ref "IC6") (pin "10") (pinfunction "Y2_10") (pintype "output"))
      (node (ref "U$1") (pin "P48") (pinfunction "P48_P48") (pintype "bidirectional"))
    )
    (net (code "53") (name "/D39") (class "Default")
      (node (ref "D39") (pin "A") (pinfunction "A_A") (pintype "passive"))
      (node (ref "IC6") (pin "9") (pinfunction "Y3_9") (pintype "output"))
      (node (ref "U$1") (pin "P47") (pinfunction "P47_P47") (pintype "bidirectional"))
    )
    (net (code "54") (name "/MUX0") (class "Default")
      (node (ref "IC4") (pin "11") (pinfunction "D0_11") (pintype "tri_state"))
      (node (ref "IC5") (pin "2") (pinfunction "A_2") (pintype "input"))
    )
    (net (code "55") (name "/MUX1") (class "Default")
      (node (ref "IC4") (pin "12") (pinfunction "D1_12") (pintype "tri_state"))
      (node (ref "IC5") (pin "3") (pinfunction "B_3") (pintype "input"))
    )
    (net (code "56") (name "/MUX2") (class "Default")
      (node (ref "IC4") (pin "13") (pinfunction "D2_13") (pintype "tri_state"))
      (node (ref "IC5") (pin "14") (pinfunction "A_14") (pintype "input"))
    )
    (net (code "57") (name "/MUX3") (class "Default")
      (node (ref "IC4") (pin "15") (pinfunction "D3_15") (pintype "tri_state"))
      (node (ref "IC5") (pin "13") (pinfunction "B_13") (pintype "input"))
    )
    (net (code "58") (name "/MUX4") (class "Default")
      (node (ref "IC4") (pin "16") (pinfunction "D4_16") (pintype "tri_state"))
      (node (ref "IC6") (pin "2") (pinfunction "A_2") (pintype "input"))
    )
    (net (code "59") (name "/MUX5") (class "Default")
      (node (ref "IC4") (pin "17") (pinfunction "D5_17") (pintype "tri_state"))
      (node (ref "IC6") (pin "3") (pinfunction "B_3") (pintype "input"))
    )
    (net (code "60") (name "/MUX6") (class "Default")
      (node (ref "IC4") (pin "18") (pinfunction "D6_18") (pintype "tri_state"))
      (node (ref "IC6") (pin "14") (pinfunction "A_14") (pintype "input"))
    )
    (net (code "61") (name "/MUX7") (class "Default")
      (node (ref "IC4") (pin "19") (pinfunction "D7_19") (pintype "tri_state"))
      (node (ref "IC6") (pin "13") (pinfunction "B_13") (pintype "input"))
    )
    (net (code "62") (name "/~{OE}") (class "Default")
      (node (ref "IC1") (pin "22") (pinfunction "~{OE}_22") (pintype "input"))
      (node (ref "IC2") (pin "22") (pinfunction "~{OE}_22") (pintype "input"))
      (node (ref "IC3") (pin "22") (pinfunction "~{OE}_22") (pintype "input"))
      (node (ref "IC4") (pin "22") (pinfunction "~{OE}_22") (pintype "input"))
      (node (ref "IC5") (pin "1") (pinfunction "G_1") (pintype "input"))
      (node (ref "IC5") (pin "15") (pinfunction "G_15") (pintype "input"))
      (node (ref "IC6") (pin "1") (pinfunction "G_1") (pintype "input"))
      (node (ref "IC6") (pin "15") (pinfunction "G_15") (pintype "input"))
      (node (ref "U$1") (pin "P32") (pinfunction "P32_P32") (pintype "bidirectional"))
    )
    (net (code "63") (name "/~{WE}") (class "Default")
      (node (ref "IC1") (pin "27") (pinfunction "~{WE}_27") (pintype "input"))
      (node (ref "IC2") (pin "27") (pinfunction "~{WE}_27") (pintype "input"))
      (node (ref "IC3") (pin "27") (pinfunction "~{WE}_27") (pintype "input"))
      (node (ref "IC4") (pin "27") (pinfunction "~{WE}_27") (pintype "input"))
      (node (ref "U$1") (pin "P33") (pinfunction "P33_P33") (pintype "bidirectional"))
    )
    (net (code "64") (name "GND") (class "Default")
      (node (ref "C8") (pin "-") (pinfunction "-_-") (pintype "passive"))
      (node (ref "IC1") (pin "14") (pinfunction "GND_14") (pintype "power_in"))
      (node (ref "IC1") (pin "20") (pinfunction "~{CE}_20") (pintype "input"))
      (node (ref "IC2") (pin "14") (pinfunction "GND_14") (pintype "power_in"))
      (node (ref "IC2") (pin "20") (pinfunction "~{CE}_20") (pintype "input"))
      (node (ref "IC3") (pin "14") (pinfunction "GND_14") (pintype "power_in"))
      (node (ref "IC3") (pin "20") (pinfunction "~{CE}_20") (pintype "input"))
      (node (ref "IC4") (pin "14") (pinfunction "GND_14") (pintype "power_in"))
      (node (ref "IC4") (pin "20") (pinfunction "~{CE}_20") (pintype "input"))
      (node (ref "R1") (pin "2") (pinfunction "2_2") (pintype "passive"))
      (node (ref "R10") (pin "2") (pinfunction "2_2") (pintype "passive"))
      (node (ref "R11") (pin "2") (pinfunction "2_2") (pintype "passive"))
      (node (ref "R12") (pin "2") (pinfunction "2_2") (pintype "passive"))
      (node (ref "R13") (pin "2") (pinfunction "2_2") (pintype "passive"))
      (node (ref "R14") (pin "2") (pinfunction "2_2") (pintype "passive"))
      (node (ref "R15") (pin "2") (pinfunction "2_2") (pintype "passive"))
      (node (ref "R16") (pin "2") (pinfunction "2_2") (pintype "passive"))
      (node (ref "R17") (pin "2") (pinfunction "2_2") (pintype "passive"))
      (node (ref "R18") (pin "2") (pinfunction "2_2") (pintype "passive"))
      (node (ref "R19") (pin "2") (pinfunction "2_2") (pintype "passive"))
      (node (ref "R2") (pin "2") (pinfunction "2_2") (pintype "passive"))
      (node (ref "R20") (pin "2") (pinfunction "2_2") (pintype "passive"))
      (node (ref "R21") (pin "2") (pinfunction "2_2") (pintype "passive"))
      (node (ref "R22") (pin "2") (pinfunction "2_2") (pintype "passive"))
      (node (ref "R23") (pin "2") (pinfunction "2_2") (pintype "passive"))
      (node (ref "R24") (pin "2") (pinfunction "2_2") (pintype "passive"))
      (node (ref "R25") (pin "2") (pinfunction "2_2") (pintype "passive"))
      (node (ref "R26") (pin "2") (pinfunction "2_2") (pintype "passive"))
      (node (ref "R27") (pin "2") (pinfunction "2_2") (pintype "passive"))
      (node (ref "R28") (pin "2") (pinfunction "2_2") (pintype "passive"))
      (node (ref "R29") (pin "2") (pinfunction "2_2") (pintype "passive"))
      (node (ref "R3") (pin "2") (pinfunction "2_2") (pintype "passive"))
      (node (ref "R30") (pin "2") (pinfunction "2_2") (pintype "passive"))
      (node (ref "R31") (pin "2") (pinfunction "2_2") (pintype "passive"))
      (node (ref "R32") (pin "2") (pinfunction "2_2") (pintype "passive"))
      (node (ref "R33") (pin "2") (pinfunction "2_2") (pintype "passive"))
      (node (ref "R34") (pin "2") (pinfunction "2_2") (pintype "passive"))
      (node (ref "R35") (pin "2") (pinfunction "2_2") (pintype "passive"))
      (node (ref "R36") (pin "2") (pinfunction "2_2") (pintype "passive"))
      (node (ref "R37") (pin "2") (pinfunction "2_2") (pintype "passive"))
      (node (ref "R38") (pin "2") (pinfunction "2_2") (pintype "passive"))
      (node (ref "R39") (pin "2") (pinfunction "2_2") (pintype "passive"))
      (node (ref "R4") (pin "2") (pinfunction "2_2") (pintype "passive"))
      (node (ref "R40") (pin "2") (pinfunction "2_2") (pintype "passive"))
      (node (ref "R5") (pin "2") (pinfunction "2_2") (pintype "passive"))
      (node (ref "R6") (pin "2") (pinfunction "2_2") (pintype "passive"))
      (node (ref "R7") (pin "2") (pinfunction "2_2") (pintype "passive"))
      (node (ref "R8") (pin "2") (pinfunction "2_2") (pintype "passive"))
      (node (ref "R9") (pin "2") (pinfunction "2_2") (pintype "passive"))
      (node (ref "U$1") (pin "P29") (pinfunction "P29_P29") (pintype "bidirectional"))
      (node (ref "U$1") (pin "P30") (pinfunction "P30_P30") (pintype "bidirectional"))
      (node (ref "U$2") (pin "P-") (pinfunction "P-_P-") (pintype "bidirectional"))
      (node (ref "U$3") (pin "P-") (pinfunction "P-_P-") (pintype "bidirectional"))
      (node (ref "U$4") (pin "P-") (pinfunction "P-_P-") (pintype "bidirectional"))
      (node (ref "U$5") (pin "P-") (pinfunction "P-_P-") (pintype "bidirectional"))
      (node (ref "U$6") (pin "P-") (pinfunction "P-_P-") (pintype "bidirectional"))
      (node (ref "U$7") (pin "P-") (pinfunction "P-_P-") (pintype "bidirectional"))
    )
    (net (code "65") (name "Net-(D0-PadC)") (class "Default")
      (node (ref "D0") (pin "C") (pinfunction "C_C") (pintype "passive"))
      (node (ref "R1") (pin "1") (pinfunction "1_1") (pintype "passive"))
    )
    (net (code "66") (name "Net-(D1-PadC)") (class "Default")
      (node (ref "D1") (pin "C") (pinfunction "C_C") (pintype "passive"))
      (node (ref "R2") (pin "1") (pinfunction "1_1") (pintype "passive"))
    )
    (net (code "67") (name "Net-(D2-PadC)") (class "Default")
      (node (ref "D2") (pin "C") (pinfunction "C_C") (pintype "passive"))
      (node (ref "R3") (pin "1") (pinfunction "1_1") (pintype "passive"))
    )
    (net (code "68") (name "Net-(D3-PadC)") (class "Default")
      (node (ref "D3") (pin "C") (pinfunction "C_C") (pintype "passive"))
      (node (ref "R4") (pin "1") (pinfunction "1_1") (pintype "passive"))
    )
    (net (code "69") (name "Net-(D4-PadC)") (class "Default")
      (node (ref "D4") (pin "C") (pinfunction "C_C") (pintype "passive"))
      (node (ref "R5") (pin "1") (pinfunction "1_1") (pintype "passive"))
    )
    (net (code "70") (name "Net-(D5-PadC)") (class "Default")
      (node (ref "D5") (pin "C") (pinfunction "C_C") (pintype "passive"))
      (node (ref "R6") (pin "1") (pinfunction "1_1") (pintype "passive"))
    )
    (net (code "71") (name "Net-(D6-PadC)") (class "Default")
      (node (ref "D6") (pin "C") (pinfunction "C_C") (pintype "passive"))
      (node (ref "R7") (pin "1") (pinfunction "1_1") (pintype "passive"))
    )
    (net (code "72") (name "Net-(D7-PadC)") (class "Default")
      (node (ref "D7") (pin "C") (pinfunction "C_C") (pintype "passive"))
      (node (ref "R8") (pin "1") (pinfunction "1_1") (pintype "passive"))
    )
    (net (code "73") (name "Net-(D8-PadC)") (class "Default")
      (node (ref "D8") (pin "C") (pinfunction "C_C") (pintype "passive"))
      (node (ref "R9") (pin "1") (pinfunction "1_1") (pintype "passive"))
    )
    (net (code "74") (name "Net-(D9-PadC)") (class "Default")
      (node (ref "D9") (pin "C") (pinfunction "C_C") (pintype "passive"))
      (node (ref "R10") (pin "1") (pinfunction "1_1") (pintype "passive"))
    )
    (net (code "75") (name "Net-(D10-PadC)") (class "Default")
      (node (ref "D10") (pin "C") (pinfunction "C_C") (pintype "passive"))
      (node (ref "R11") (pin "1") (pinfunction "1_1") (pintype "passive"))
    )
    (net (code "76") (name "Net-(D11-PadC)") (class "Default")
      (node (ref "D11") (pin "C") (pinfunction "C_C") (pintype "passive"))
      (node (ref "R12") (pin "1") (pinfunction "1_1") (pintype "passive"))
    )
    (net (code "77") (name "Net-(D12-PadC)") (class "Default")
      (node (ref "D12") (pin "C") (pinfunction "C_C") (pintype "passive"))
      (node (ref "R13") (pin "1") (pinfunction "1_1") (pintype "passive"))
    )
    (net (code "78") (name "Net-(D13-PadC)") (class "Default")
      (node (ref "D13") (pin "C") (pinfunction "C_C") (pintype "passive"))
      (node (ref "R14") (pin "1") (pinfunction "1_1") (pintype "passive"))
    )
    (net (code "79") (name "Net-(D14-PadC)") (class "Default")
      (node (ref "D14") (pin "C") (pinfunction "C_C") (pintype "passive"))
      (node (ref "R15") (pin "1") (pinfunction "1_1") (pintype "passive"))
    )
    (net (code "80") (name "Net-(D15-PadC)") (class "Default")
      (node (ref "D15") (pin "C") (pinfunction "C_C") (pintype "passive"))
      (node (ref "R16") (pin "1") (pinfunction "1_1") (pintype "passive"))
    )
    (net (code "81") (name "Net-(D16-PadC)") (class "Default")
      (node (ref "D16") (pin "C") (pinfunction "C_C") (pintype "passive"))
      (node (ref "R17") (pin "1") (pinfunction "1_1") (pintype "passive"))
    )
    (net (code "82") (name "Net-(D17-PadC)") (class "Default")
      (node (ref "D17") (pin "C") (pinfunction "C_C") (pintype "passive"))
      (node (ref "R18") (pin "1") (pinfunction "1_1") (pintype "passive"))
    )
    (net (code "83") (name "Net-(D18-PadC)") (class "Default")
      (node (ref "D18") (pin "C") (pinfunction "C_C") (pintype "passive"))
      (node (ref "R19") (pin "1") (pinfunction "1_1") (pintype "passive"))
    )
    (net (code "84") (name "Net-(D19-PadC)") (class "Default")
      (node (ref "D19") (pin "C") (pinfunction "C_C") (pintype "passive"))
      (node (ref "R20") (pin "1") (pinfunction "1_1") (pintype "passive"))
    )
    (net (code "85") (name "Net-(D20-PadC)") (class "Default")
      (node (ref "D20") (pin "C") (pinfunction "C_C") (pintype "passive"))
      (node (ref "R21") (pin "1") (pinfunction "1_1") (pintype "passive"))
    )
    (net (code "86") (name "Net-(D21-PadC)") (class "Default")
      (node (ref "D21") (pin "C") (pinfunction "C_C") (pintype "passive"))
      (node (ref "R22") (pin "1") (pinfunction "1_1") (pintype "passive"))
    )
    (net (code "87") (name "Net-(D22-PadC)") (class "Default")
      (node (ref "D22") (pin "C") (pinfunction "C_C") (pintype "passive"))
      (node (ref "R23") (pin "1") (pinfunction "1_1") (pintype "passive"))
    )
    (net (code "88") (name "Net-(D23-PadC)") (class "Default")
      (node (ref "D23") (pin "C") (pinfunction "C_C") (pintype "passive"))
      (node (ref "R24") (pin "1") (pinfunction "1_1") (pintype "passive"))
    )
    (net (code "89") (name "Net-(D24-PadC)") (class "Default")
      (node (ref "D24") (pin "C") (pinfunction "C_C") (pintype "passive"))
      (node (ref "R25") (pin "1") (pinfunction "1_1") (pintype "passive"))
    )
    (net (code "90") (name "Net-(D25-PadC)") (class "Default")
      (node (ref "D25") (pin "C") (pinfunction "C_C") (pintype "passive"))
      (node (ref "R26") (pin "1") (pinfunction "1_1") (pintype "passive"))
    )
    (net (code "91") (name "Net-(D26-PadC)") (class "Default")
      (node (ref "D26") (pin "C") (pinfunction "C_C") (pintype "passive"))
      (node (ref "R27") (pin "1") (pinfunction "1_1") (pintype "passive"))
    )
    (net (code "92") (name "Net-(D27-PadC)") (class "Default")
      (node (ref "D27") (pin "C") (pinfunction "C_C") (pintype "passive"))
      (node (ref "R28") (pin "1") (pinfunction "1_1") (pintype "passive"))
    )
    (net (code "93") (name "Net-(D28-PadC)") (class "Default")
      (node (ref "D28") (pin "C") (pinfunction "C_C") (pintype "passive"))
      (node (ref "R29") (pin "1") (pinfunction "1_1") (pintype "passive"))
    )
    (net (code "94") (name "Net-(D29-PadC)") (class "Default")
      (node (ref "D29") (pin "C") (pinfunction "C_C") (pintype "passive"))
      (node (ref "R30") (pin "1") (pinfunction "1_1") (pintype "passive"))
    )
    (net (code "95") (name "Net-(D30-PadC)") (class "Default")
      (node (ref "D30") (pin "C") (pinfunction "C_C") (pintype "passive"))
      (node (ref "R31") (pin "1") (pinfunction "1_1") (pintype "passive"))
    )
    (net (code "96") (name "Net-(D31-PadC)") (class "Default")
      (node (ref "D31") (pin "C") (pinfunction "C_C") (pintype "passive"))
      (node (ref "R32") (pin "1") (pinfunction "1_1") (pintype "passive"))
    )
    (net (code "97") (name "Net-(D32-PadC)") (class "Default")
      (node (ref "D32") (pin "C") (pinfunction "C_C") (pintype "passive"))
      (node (ref "R33") (pin "1") (pinfunction "1_1") (pintype "passive"))
    )
    (net (code "98") (name "Net-(D33-PadC)") (class "Default")
      (node (ref "D33") (pin "C") (pinfunction "C_C") (pintype "passive"))
      (node (ref "R34") (pin "1") (pinfunction "1_1") (pintype "passive"))
    )
    (net (code "99") (name "Net-(D34-PadC)") (class "Default")
      (node (ref "D34") (pin "C") (pinfunction "C_C") (pintype "passive"))
      (node (ref "R35") (pin "1") (pinfunction "1_1") (pintype "passive"))
    )
    (net (code "100") (name "Net-(D35-PadC)") (class "Default")
      (node (ref "D35") (pin "C") (pinfunction "C_C") (pintype "passive"))
      (node (ref "R36") (pin "1") (pinfunction "1_1") (pintype "passive"))
    )
    (net (code "101") (name "Net-(D36-PadC)") (class "Default")
      (node (ref "D36") (pin "C") (pinfunction "C_C") (pintype "passive"))
      (node (ref "R37") (pin "1") (pinfunction "1_1") (pintype "passive"))
    )
    (net (code "102") (name "Net-(D37-PadC)") (class "Default")
      (node (ref "D37") (pin "C") (pinfunction "C_C") (pintype "passive"))
      (node (ref "R38") (pin "1") (pinfunction "1_1") (pintype "passive"))
    )
    (net (code "103") (name "Net-(D38-PadC)") (class "Default")
      (node (ref "D38") (pin "C") (pinfunction "C_C") (pintype "passive"))
      (node (ref "R39") (pin "1") (pinfunction "1_1") (pintype "passive"))
    )
    (net (code "104") (name "Net-(D39-PadC)") (class "Default")
      (node (ref "D39") (pin "C") (pinfunction "C_C") (pintype "passive"))
      (node (ref "R40") (pin "1") (pinfunction "1_1") (pintype "passive"))
    )
    (net (code "105") (name "VCC") (class "Default")
      (node (ref "C8") (pin "+") (pinfunction "+_+") (pintype "passive"))
      (node (ref "IC1") (pin "28") (pinfunction "VCC_28") (pintype "power_in"))
      (node (ref "IC2") (pin "28") (pinfunction "VCC_28") (pintype "power_in"))
      (node (ref "IC3") (pin "28") (pinfunction "VCC_28") (pintype "power_in"))
      (node (ref "IC4") (pin "28") (pinfunction "VCC_28") (pintype "power_in"))
      (node (ref "U$1") (pin "P0") (pinfunction "P0_P0") (pintype "bidirectional"))
      (node (ref "U$1") (pin "P59") (pinfunction "P59_P59") (pintype "bidirectional"))
      (node (ref "U$2") (pin "P+") (pinfunction "P+_P+") (pintype "bidirectional"))
      (node (ref "U$3") (pin "P+") (pinfunction "P+_P+") (pintype "bidirectional"))
      (node (ref "U$4") (pin "P+") (pinfunction "P+_P+") (pintype "bidirectional"))
      (node (ref "U$5") (pin "P+") (pinfunction "P+_P+") (pintype "bidirectional"))
      (node (ref "U$6") (pin "P+") (pinfunction "P+_P+") (pintype "bidirectional"))
      (node (ref "U$7") (pin "P+") (pinfunction "P+_P+") (pintype "bidirectional"))
    )
    (net (code "106") (name "unconnected-(IC1-RDY{slash}~{BSY}-Pad1)") (class "Default")
      (node (ref "IC1") (pin "1") (pinfunction "RDY/~{BSY}_1") (pintype "output"))
    )
    (net (code "107") (name "unconnected-(IC2-RDY{slash}~{BSY}-Pad1)") (class "Default")
      (node (ref "IC2") (pin "1") (pinfunction "RDY/~{BSY}_1") (pintype "output"))
    )
    (net (code "108") (name "unconnected-(IC3-RDY{slash}~{BSY}-Pad1)") (class "Default")
      (node (ref "IC3") (pin "1") (pinfunction "RDY/~{BSY}_1") (pintype "output"))
    )
    (net (code "109") (name "unconnected-(IC4-RDY{slash}~{BSY}-Pad1)") (class "Default")
      (node (ref "IC4") (pin "1") (pinfunction "RDY/~{BSY}_1") (pintype "output"))
    )
    (net (code "110") (name "unconnected-(U$1-PadP31)") (class "Default")
      (node (ref "U$1") (pin "P31") (pinfunction "P31_P31") (pintype "bidirectional"))
    )
  )
)
